# Adafruit_PowerRelay_Wing.net
KiCad netlist of a schematic drawn in EAGLE
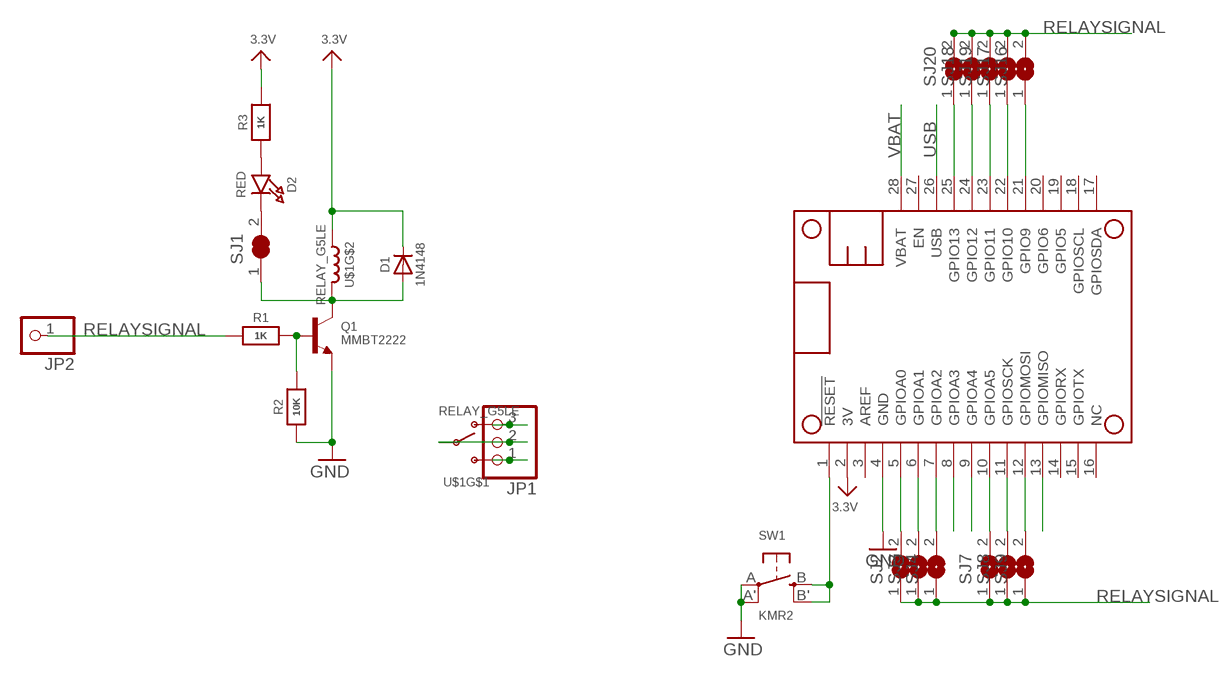
[diagram p0: schematic, sheet 1]

(export (version "E")
  (design (tool "Eeschema 10.0.6"))
  (components
    (comp (ref "D1")
      (value "1N4148")
      (footprint "eagle-import:SOD-323")
      (libsource (lib "eagle-import") (part "DIODESOD-323"))
    )
    (comp (ref "D2")
      (value "RED")
      (footprint "eagle-import:CHIPLED_0805_NOOUTLINE")
      (libsource (lib "eagle-import") (part "LED0805_NOOUTLINE"))
    )
    (comp (ref "JP1")
      (value "HEADER-1X3_508TERM")
      (footprint "eagle-import:TERMBLOCK_1X3_5.08MM")
      (libsource (lib "eagle-import") (part "HEADER-1X3_508TERM"))
    )
    (comp (ref "JP2")
      (value "HEADER-1X1ROUND")
      (footprint "eagle-import:1X01_ROUND")
      (libsource (lib "eagle-import") (part "HEADER-1X1ROUND"))
    )
    (comp (ref "MS2")
      (value "FEATHERWING")
      (footprint "eagle-import:FEATHERWING")
      (libsource (lib "eagle-import") (part "FEATHERWING"))
    )
    (comp (ref "Q1")
      (value "MMBT2222")
      (footprint "eagle-import:SOT23-R")
      (libsource (lib "eagle-import") (part "TRANSISTOR_NPN"))
    )
    (comp (ref "R1")
      (value "1K")
      (footprint "eagle-import:0805-NO")
      (libsource (lib "eagle-import") (part "RESISTOR0805_NOOUTLINE"))
    )
    (comp (ref "R2")
      (value "10K")
      (footprint "eagle-import:0805-NO")
      (libsource (lib "eagle-import") (part "RESISTOR0805_NOOUTLINE"))
    )
    (comp (ref "R3")
      (value "1K")
      (footprint "eagle-import:0805-NO")
      (libsource (lib "eagle-import") (part "RESISTOR0805_NOOUTLINE"))
    )
    (comp (ref "SJ1")
      (value "SOLDERJUMPER_CLOSED")
      (footprint "eagle-import:SOLDERJUMPER_CLOSEDWIRE")
      (libsource (lib "eagle-import") (part "SOLDERJUMPER_CLOSED"))
    )
    (comp (ref "SJ2")
      (value "SOLDERJUMPER")
      (footprint "eagle-import:SOLDERJUMPER_ARROW_NOPASTE")
      (libsource (lib "eagle-import") (part "SOLDERJUMPER"))
    )
    (comp (ref "SJ3")
      (value "SOLDERJUMPER")
      (footprint "eagle-import:SOLDERJUMPER_ARROW_NOPASTE")
      (libsource (lib "eagle-import") (part "SOLDERJUMPER"))
    )
    (comp (ref "SJ4")
      (value "SOLDERJUMPER")
      (footprint "eagle-import:SOLDERJUMPER_ARROW_NOPASTE")
      (libsource (lib "eagle-import") (part "SOLDERJUMPER"))
    )
    (comp (ref "SJ7")
      (value "SOLDERJUMPER")
      (footprint "eagle-import:SOLDERJUMPER_ARROW_NOPASTE")
      (libsource (lib "eagle-import") (part "SOLDERJUMPER"))
    )
    (comp (ref "SJ8")
      (value "SOLDERJUMPER")
      (footprint "eagle-import:SOLDERJUMPER_ARROW_NOPASTE")
      (libsource (lib "eagle-import") (part "SOLDERJUMPER"))
    )
    (comp (ref "SJ9")
      (value "SOLDERJUMPER")
      (footprint "eagle-import:SOLDERJUMPER_ARROW_NOPASTE")
      (libsource (lib "eagle-import") (part "SOLDERJUMPER"))
    )
    (comp (ref "SJ16")
      (value "SOLDERJUMPER")
      (footprint "eagle-import:SOLDERJUMPER_ARROW_NOPASTE")
      (libsource (lib "eagle-import") (part "SOLDERJUMPER"))
    )
    (comp (ref "SJ17")
      (value "SOLDERJUMPER")
      (footprint "eagle-import:SOLDERJUMPER_ARROW_NOPASTE")
      (libsource (lib "eagle-import") (part "SOLDERJUMPER"))
    )
    (comp (ref "SJ18")
      (value "SOLDERJUMPER")
      (footprint "eagle-import:SOLDERJUMPER_ARROW_NOPASTE")
      (libsource (lib "eagle-import") (part "SOLDERJUMPER"))
    )
    (comp (ref "SJ19")
      (value "SOLDERJUMPER")
      (footprint "eagle-import:SOLDERJUMPER_ARROW_NOPASTE")
      (libsource (lib "eagle-import") (part "SOLDERJUMPER"))
    )
    (comp (ref "SJ20")
      (value "SOLDERJUMPER")
      (footprint "eagle-import:SOLDERJUMPER_ARROW_NOPASTE")
      (libsource (lib "eagle-import") (part "SOLDERJUMPER"))
    )
    (comp (ref "SW1")
      (value "KMR2")
      (footprint "eagle-import:BTN_KMR2_4.6X2.8")
      (libsource (lib "eagle-import") (part "SWITCH_TACT_SMT4.6X2.8"))
    )
    (comp (ref "U$1")
      (value "RELAY_G5LE")
      (footprint "eagle-import:RELAY_G5LE-1")
      (libsource (lib "eagle-import") (part "RELAY_G5LE"))
    )
  )
  (nets
    (net (code "1") (name "/RELAYSIGNAL") (class "Default")
      (node (ref "JP2") (pin "1") (pinfunction "1_1") (pintype "passive"))
      (node (ref "R1") (pin "1") (pinfunction "1_1") (pintype "passive"))
      (node (ref "SJ16") (pin "2") (pinfunction "2_2") (pintype "passive"))
      (node (ref "SJ17") (pin "2") (pinfunction "2_2") (pintype "passive"))
      (node (ref "SJ18") (pin "2") (pinfunction "2_2") (pintype "passive"))
      (node (ref "SJ19") (pin "2") (pinfunction "2_2") (pintype "passive"))
      (node (ref "SJ2") (pin "1") (pinfunction "1_1") (pintype "passive"))
      (node (ref "SJ20") (pin "2") (pinfunction "2_2") (pintype "passive"))
      (node (ref "SJ3") (pin "1") (pinfunction "1_1") (pintype "passive"))
      (node (ref "SJ4") (pin "1") (pinfunction "1_1") (pintype "passive"))
      (node (ref "SJ7") (pin "1") (pinfunction "1_1") (pintype "passive"))
      (node (ref "SJ8") (pin "1") (pinfunction "1_1") (pintype "passive"))
      (node (ref "SJ9") (pin "1") (pinfunction "1_1") (pintype "passive"))
    )
    (net (code "2") (name "/USB") (class "Default")
      (node (ref "MS2") (pin "26") (pinfunction "USB_26") (pintype "power_in"))
    )
    (net (code "3") (name "/VBAT") (class "Default")
      (node (ref "MS2") (pin "28") (pinfunction "VBAT_28") (pintype "power_in"))
    )
    (net (code "4") (name "3.3V") (class "Default")
      (node (ref "D1") (pin "C") (pinfunction "C_C") (pintype "passive"))
      (node (ref "MS2") (pin "2") (pinfunction "3V_2") (pintype "power_in"))
      (node (ref "R3") (pin "2") (pinfunction "2_2") (pintype "passive"))
      (node (ref "U$1") (pin "2") (pinfunction "1_2") (pintype "passive"))
    )
    (net (code "5") (name "GND") (class "Default")
      (node (ref "MS2") (pin "4") (pinfunction "GND_4") (pintype "power_in"))
      (node (ref "Q1") (pin "2") (pinfunction "E_2") (pintype "passive"))
      (node (ref "R2") (pin "1") (pinfunction "1_1") (pintype "passive"))
      (node (ref "SW1") (pin "A") (pinfunction "P_A") (pintype "passive"))
      (node (ref "SW1") (pin "A'") (pinfunction "P1_A'") (pintype "passive"))
    )
    (net (code "6") (name "Net-(D2-PadA)") (class "Default")
      (node (ref "D2") (pin "A") (pinfunction "A_A") (pintype "passive"))
      (node (ref "R3") (pin "1") (pinfunction "1_1") (pintype "passive"))
    )
    (net (code "7") (name "Net-(D2-PadC)") (class "Default")
      (node (ref "D2") (pin "C") (pinfunction "C_C") (pintype "passive"))
      (node (ref "SJ1") (pin "2") (pinfunction "2_2") (pintype "passive"))
    )
    (net (code "8") (name "Net-(MS2-GPIO9)") (class "Default")
      (node (ref "MS2") (pin "21") (pinfunction "GPIO9_21") (pintype "bidirectional"))
      (node (ref "SJ16") (pin "1") (pinfunction "1_1") (pintype "passive"))
    )
    (net (code "9") (name "Net-(MS2-GPIO10)") (class "Default")
      (node (ref "MS2") (pin "22") (pinfunction "GPIO10_22") (pintype "bidirectional"))
      (node (ref "SJ17") (pin "1") (pinfunction "1_1") (pintype "passive"))
    )
    (net (code "10") (name "Net-(MS2-GPIO11)") (class "Default")
      (node (ref "MS2") (pin "23") (pinfunction "GPIO11_23") (pintype "bidirectional"))
      (node (ref "SJ19") (pin "1") (pinfunction "1_1") (pintype "passive"))
    )
    (net (code "11") (name "Net-(MS2-GPIO12)") (class "Default")
      (node (ref "MS2") (pin "24") (pinfunction "GPIO12_24") (pintype "bidirectional"))
      (node (ref "SJ18") (pin "1") (pinfunction "1_1") (pintype "passive"))
    )
    (net (code "12") (name "Net-(MS2-GPIO13)") (class "Default")
      (node (ref "MS2") (pin "25") (pinfunction "GPIO13_25") (pintype "bidirectional"))
      (node (ref "SJ20") (pin "1") (pinfunction "1_1") (pintype "passive"))
    )
    (net (code "13") (name "Net-(MS2-GPIOA0)") (class "Default")
      (node (ref "MS2") (pin "5") (pinfunction "GPIOA0_5") (pintype "bidirectional"))
      (node (ref "SJ2") (pin "2") (pinfunction "2_2") (pintype "passive"))
    )
    (net (code "14") (name "Net-(MS2-GPIOA1)") (class "Default")
      (node (ref "MS2") (pin "6") (pinfunction "GPIOA1_6") (pintype "bidirectional"))
      (node (ref "SJ3") (pin "2") (pinfunction "2_2") (pintype "passive"))
    )
    (net (code "15") (name "Net-(MS2-GPIOA2)") (class "Default")
      (node (ref "MS2") (pin "7") (pinfunction "GPIOA2_7") (pintype "bidirectional"))
      (node (ref "SJ4") (pin "2") (pinfunction "2_2") (pintype "passive"))
    )
    (net (code "16") (name "Net-(MS2-GPIOA5)") (class "Default")
      (node (ref "MS2") (pin "10") (pinfunction "GPIOA5_10") (pintype "bidirectional"))
      (node (ref "SJ7") (pin "2") (pinfunction "2_2") (pintype "passive"))
    )
    (net (code "17") (name "Net-(MS2-GPIOMOSI)") (class "Default")
      (node (ref "MS2") (pin "12") (pinfunction "GPIOMOSI_12") (pintype "bidirectional"))
      (node (ref "SJ9") (pin "2") (pinfunction "2_2") (pintype "passive"))
    )
    (net (code "18") (name "Net-(MS2-GPIOSCK)") (class "Default")
      (node (ref "MS2") (pin "11") (pinfunction "GPIOSCK_11") (pintype "bidirectional"))
      (node (ref "SJ8") (pin "2") (pinfunction "2_2") (pintype "passive"))
    )
    (net (code "19") (name "Net-(MS2-~{RESET})") (class "Default")
      (node (ref "MS2") (pin "1") (pinfunction "~{RESET}_1") (pintype "input"))
      (node (ref "SW1") (pin "B") (pinfunction "S_B") (pintype "passive"))
      (node (ref "SW1") (pin "B'") (pinfunction "S1_B'") (pintype "passive"))
    )
    (net (code "20") (name "Net-(Q1-B)") (class "Default")
      (node (ref "Q1") (pin "1") (pinfunction "B_1") (pintype "passive"))
      (node (ref "R1") (pin "2") (pinfunction "2_2") (pintype "passive"))
      (node (ref "R2") (pin "2") (pinfunction "2_2") (pintype "passive"))
    )
    (net (code "21") (name "Net-(Q1-C)") (class "Default")
      (node (ref "D1") (pin "A") (pinfunction "A_A") (pintype "passive"))
      (node (ref "Q1") (pin "3") (pinfunction "C_3") (pintype "passive"))
      (node (ref "SJ1") (pin "1") (pinfunction "1_1") (pintype "passive"))
      (node (ref "U$1") (pin "5") (pinfunction "2_5") (pintype "passive"))
    )
    (net (code "22") (name "Net-(U$1A-O)") (class "Default")
      (node (ref "JP1") (pin "3") (pinfunction "3_3") (pintype "passive"))
      (node (ref "U$1") (pin "3") (pinfunction "O_3") (pintype "passive"))
    )
    (net (code "23") (name "Net-(U$1A-P)") (class "Default")
      (node (ref "JP1") (pin "2") (pinfunction "2_2") (pintype "passive"))
      (node (ref "U$1") (pin "1") (pinfunction "P_1") (pintype "passive"))
    )
    (net (code "24") (name "Net-(U$1A-S)") (class "Default")
      (node (ref "JP1") (pin "1") (pinfunction "1_1") (pintype "passive"))
      (node (ref "U$1") (pin "4") (pinfunction "S_4") (pintype "passive"))
    )
    (net (code "25") (name "unconnected-(MS2-AREF-Pad3)") (class "Default")
      (node (ref "MS2") (pin "3") (pinfunction "AREF_3") (pintype "passive"))
    )
    (net (code "26") (name "unconnected-(MS2-EN-Pad27)") (class "Default")
      (node (ref "MS2") (pin "27") (pinfunction "EN_27") (pintype "passive"))
    )
    (net (code "27") (name "unconnected-(MS2-GPIO5-Pad19)") (class "Default")
      (node (ref "MS2") (pin "19") (pinfunction "GPIO5_19") (pintype "bidirectional"))
    )
    (net (code "28") (name "unconnected-(MS2-GPIO6-Pad20)") (class "Default")
      (node (ref "MS2") (pin "20") (pinfunction "GPIO6_20") (pintype "bidirectional"))
    )
    (net (code "29") (name "unconnected-(MS2-GPIOA3-Pad8)") (class "Default")
      (node (ref "MS2") (pin "8") (pinfunction "GPIOA3_8") (pintype "bidirectional"))
    )
    (net (code "30") (name "unconnected-(MS2-GPIOA4-Pad9)") (class "Default")
      (node (ref "MS2") (pin "9") (pinfunction "GPIOA4_9") (pintype "bidirectional"))
    )
    (net (code "31") (name "unconnected-(MS2-GPIOMISO-Pad13)") (class "Default")
      (node (ref "MS2") (pin "13") (pinfunction "GPIOMISO_13") (pintype "bidirectional"))
    )
    (net (code "32") (name "unconnected-(MS2-GPIORX-Pad14)") (class "Default")
      (node (ref "MS2") (pin "14") (pinfunction "GPIORX_14") (pintype "bidirectional"))
    )
    (net (code "33") (name "unconnected-(MS2-GPIOSCL-Pad18)") (class "Default")
      (node (ref "MS2") (pin "18") (pinfunction "GPIOSCL_18") (pintype "bidirectional"))
    )
    (net (code "34") (name "unconnected-(MS2-GPIOSDA-Pad17)") (class "Default")
      (node (ref "MS2") (pin "17") (pinfunction "GPIOSDA_17") (pintype "bidirectional"))
    )
    (net (code "35") (name "unconnected-(MS2-GPIOTX-Pad15)") (class "Default")
      (node (ref "MS2") (pin "15") (pinfunction "GPIOTX_15") (pintype "bidirectional"))
    )
    (net (code "36") (name "unconnected-(MS2-NC-Pad16)") (class "Default")
      (node (ref "MS2") (pin "16") (pinfunction "NC_16") (pintype "passive"))
    )
  )
)
